# Attenuverter_v1_SCH.net
KiCad netlist of a schematic drawn in Altium Designer
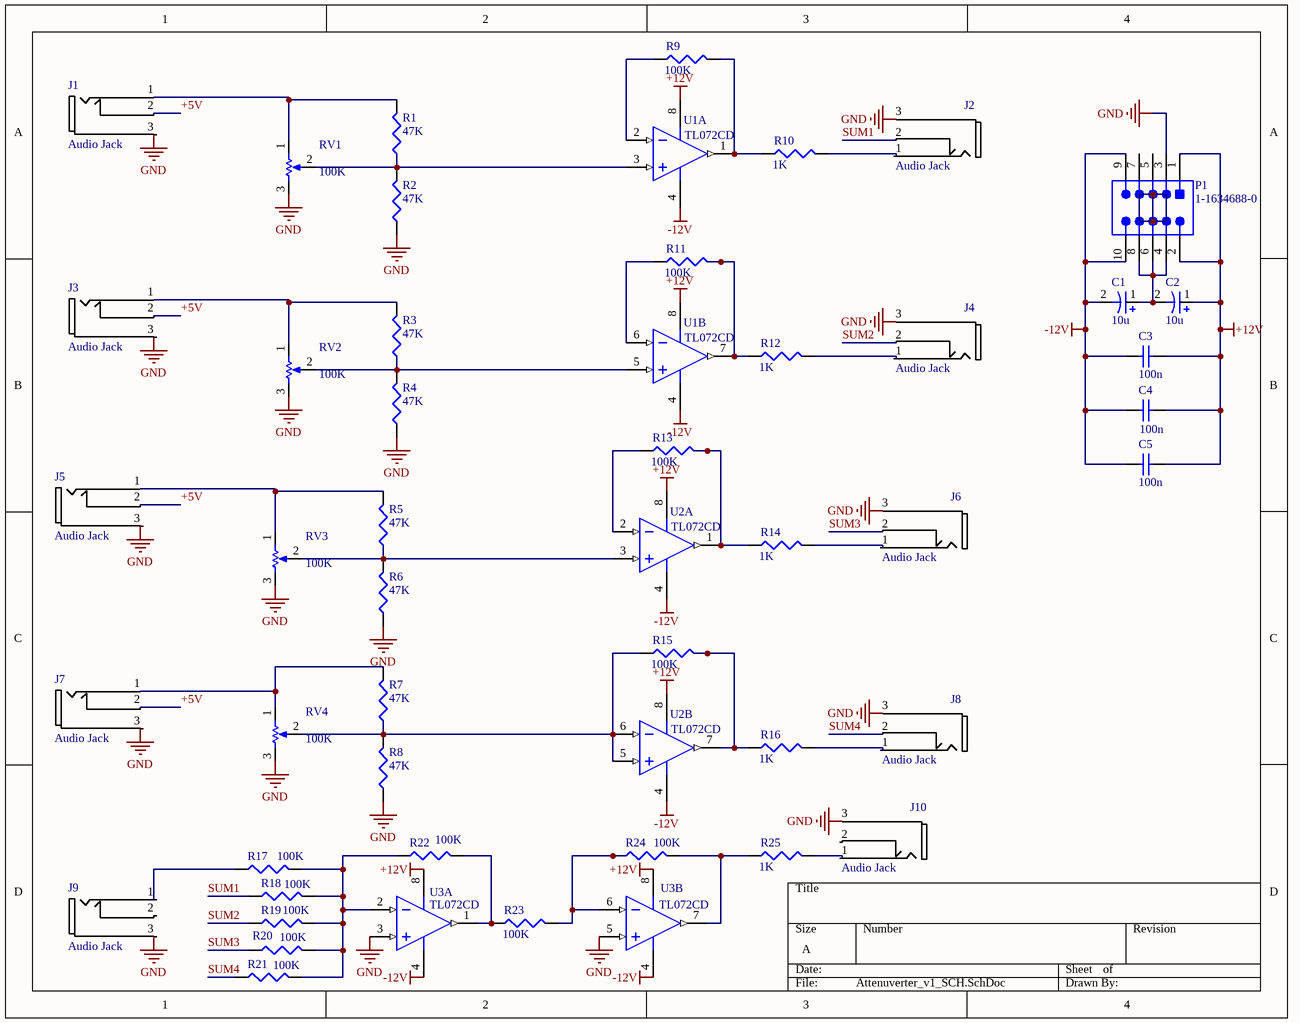
[diagram p0: Attenuverter_v1_SCH.SchDoc]

(export (version "E")
  (design (tool "Eeschema 10.0.6"))
  (components
    (comp (ref "C1")
      (value "10u")
      (footprint "SMD-1210C")
      (description "Polarized Capacitor (Radial)")
      (fields (field (name "Comment") "Cap Pol1") (field (name "PUBLISHER") "Altium Limited"))
      (libsource (lib "Miscellaneous Devices") (part "Cap Pol1"))
    )
    (comp (ref "C2")
      (value "10u")
      (footprint "SMD-1210C")
      (description "Polarized Capacitor (Radial)")
      (fields (field (name "Comment") "Cap Pol1") (field (name "PUBLISHER") "Altium Limited"))
      (libsource (lib "Miscellaneous Devices") (part "Cap Pol1"))
    )
    (comp (ref "C3")
      (value "100n")
      (footprint "0603")
      (description "Capacitor")
      (fields (field (name "Comment") "Cap") (field (name "PUBLISHER") "Altium Limited"))
      (libsource (lib "Miscellaneous Devices") (part "Cap"))
    )
    (comp (ref "C4")
      (value "100n")
      (footprint "0603")
      (description "Capacitor")
      (fields (field (name "Comment") "Cap") (field (name "PUBLISHER") "Altium Limited"))
      (libsource (lib "Miscellaneous Devices") (part "Cap"))
    )
    (comp (ref "C5")
      (value "100n")
      (footprint "0603")
      (description "Capacitor")
      (fields (field (name "Comment") "Cap") (field (name "PUBLISHER") "Altium Limited"))
      (libsource (lib "Miscellaneous Devices") (part "Cap"))
    )
    (comp (ref "J1")
      (value "Audio Jack")
      (footprint "Audio Jack")
      (libsource (lib "DIYSynth") (part "Audio Jack"))
    )
    (comp (ref "J2")
      (value "Audio Jack")
      (footprint "Audio Jack")
      (libsource (lib "DIYSynth") (part "Audio Jack"))
    )
    (comp (ref "J3")
      (value "Audio Jack")
      (footprint "Audio Jack")
      (libsource (lib "DIYSynth") (part "Audio Jack"))
    )
    (comp (ref "J4")
      (value "Audio Jack")
      (footprint "Audio Jack")
      (libsource (lib "DIYSynth") (part "Audio Jack"))
    )
    (comp (ref "J5")
      (value "Audio Jack")
      (footprint "Audio Jack")
      (libsource (lib "DIYSynth") (part "Audio Jack"))
    )
    (comp (ref "J6")
      (value "Audio Jack")
      (footprint "Audio Jack")
      (libsource (lib "DIYSynth") (part "Audio Jack"))
    )
    (comp (ref "J7")
      (value "Audio Jack")
      (footprint "Audio Jack")
      (libsource (lib "DIYSynth") (part "Audio Jack"))
    )
    (comp (ref "J8")
      (value "Audio Jack")
      (footprint "Audio Jack")
      (libsource (lib "DIYSynth") (part "Audio Jack"))
    )
    (comp (ref "J9")
      (value "Audio Jack")
      (footprint "Audio Jack")
      (libsource (lib "DIYSynth") (part "Audio Jack"))
    )
    (comp (ref "J10")
      (value "Audio Jack")
      (footprint "Audio Jack")
      (libsource (lib "DIYSynth") (part "Audio Jack"))
    )
    (comp (ref "P1")
      (value "1-1634688-0")
      (footprint "TECO-1-1634688-0-10_V")
      (fields (field (name "MANUFACTURER") "TE Connectivity"))
      (libsource (lib "Altium Content Vault") (part "CN-2P-M-R10"))
    )
    (comp (ref "R1")
      (value "47K")
      (footprint "J1-0603")
      (description "Resistor")
      (fields (field (name "Comment") "Res3") (field (name "PUBLISHER") "Altium Limited"))
      (libsource (lib "Miscellaneous Devices") (part "Res3"))
    )
    (comp (ref "R2")
      (value "47K")
      (footprint "J1-0603")
      (description "Resistor")
      (fields (field (name "Comment") "Res3") (field (name "PUBLISHER") "Altium Limited"))
      (libsource (lib "Miscellaneous Devices") (part "Res3"))
    )
    (comp (ref "R3")
      (value "47K")
      (footprint "J1-0603")
      (description "Resistor")
      (fields (field (name "Comment") "Res3") (field (name "PUBLISHER") "Altium Limited"))
      (libsource (lib "Miscellaneous Devices") (part "Res3"))
    )
    (comp (ref "R4")
      (value "47K")
      (footprint "J1-0603")
      (description "Resistor")
      (fields (field (name "Comment") "Res3") (field (name "PUBLISHER") "Altium Limited"))
      (libsource (lib "Miscellaneous Devices") (part "Res3"))
    )
    (comp (ref "R5")
      (value "47K")
      (footprint "J1-0603")
      (description "Resistor")
      (fields (field (name "Comment") "Res3") (field (name "PUBLISHER") "Altium Limited"))
      (libsource (lib "Miscellaneous Devices") (part "Res3"))
    )
    (comp (ref "R6")
      (value "47K")
      (footprint "J1-0603")
      (description "Resistor")
      (fields (field (name "Comment") "Res3") (field (name "PUBLISHER") "Altium Limited"))
      (libsource (lib "Miscellaneous Devices") (part "Res3"))
    )
    (comp (ref "R7")
      (value "47K")
      (footprint "J1-0603")
      (description "Resistor")
      (fields (field (name "Comment") "Res3") (field (name "PUBLISHER") "Altium Limited"))
      (libsource (lib "Miscellaneous Devices") (part "Res3"))
    )
    (comp (ref "R8")
      (value "47K")
      (footprint "J1-0603")
      (description "Resistor")
      (fields (field (name "Comment") "Res3") (field (name "PUBLISHER") "Altium Limited"))
      (libsource (lib "Miscellaneous Devices") (part "Res3"))
    )
    (comp (ref "R9")
      (value "100K")
      (footprint "J1-0603")
      (description "Resistor")
      (fields (field (name "Comment") "Res3") (field (name "PUBLISHER") "Altium Limited"))
      (libsource (lib "Miscellaneous Devices") (part "Res3"))
    )
    (comp (ref "R10")
      (value "1K")
      (footprint "J1-0603")
      (description "Resistor")
      (fields (field (name "Comment") "Res3") (field (name "PUBLISHER") "Altium Limited"))
      (libsource (lib "Miscellaneous Devices") (part "Res3"))
    )
    (comp (ref "R11")
      (value "100K")
      (footprint "J1-0603")
      (description "Resistor")
      (fields (field (name "Comment") "Res3") (field (name "PUBLISHER") "Altium Limited"))
      (libsource (lib "Miscellaneous Devices") (part "Res3"))
    )
    (comp (ref "R12")
      (value "1K")
      (footprint "J1-0603")
      (description "Resistor")
      (fields (field (name "Comment") "Res3") (field (name "PUBLISHER") "Altium Limited"))
      (libsource (lib "Miscellaneous Devices") (part "Res3"))
    )
    (comp (ref "R13")
      (value "100K")
      (footprint "J1-0603")
      (description "Resistor")
      (fields (field (name "Comment") "Res3") (field (name "PUBLISHER") "Altium Limited"))
      (libsource (lib "Miscellaneous Devices") (part "Res3"))
    )
    (comp (ref "R14")
      (value "1K")
      (footprint "J1-0603")
      (description "Resistor")
      (fields (field (name "Comment") "Res3") (field (name "PUBLISHER") "Altium Limited"))
      (libsource (lib "Miscellaneous Devices") (part "Res3"))
    )
    (comp (ref "R15")
      (value "100K")
      (footprint "J1-0603")
      (description "Resistor")
      (fields (field (name "Comment") "Res3") (field (name "PUBLISHER") "Altium Limited"))
      (libsource (lib "Miscellaneous Devices") (part "Res3"))
    )
    (comp (ref "R16")
      (value "1K")
      (footprint "J1-0603")
      (description "Resistor")
      (fields (field (name "Comment") "Res3") (field (name "PUBLISHER") "Altium Limited"))
      (libsource (lib "Miscellaneous Devices") (part "Res3"))
    )
    (comp (ref "R17")
      (value "100K")
      (footprint "J1-0603")
      (description "Resistor")
      (fields (field (name "Comment") "Res3") (field (name "PUBLISHER") "Altium Limited"))
      (libsource (lib "Miscellaneous Devices") (part "Res3"))
    )
    (comp (ref "R18")
      (value "100K")
      (footprint "J1-0603")
      (description "Resistor")
      (fields (field (name "Comment") "Res3") (field (name "PUBLISHER") "Altium Limited"))
      (libsource (lib "Miscellaneous Devices") (part "Res3"))
    )
    (comp (ref "R19")
      (value "100K")
      (footprint "J1-0603")
      (description "Resistor")
      (fields (field (name "Comment") "Res3") (field (name "PUBLISHER") "Altium Limited"))
      (libsource (lib "Miscellaneous Devices") (part "Res3"))
    )
    (comp (ref "R20")
      (value "100K")
      (footprint "J1-0603")
      (description "Resistor")
      (fields (field (name "Comment") "Res3") (field (name "PUBLISHER") "Altium Limited"))
      (libsource (lib "Miscellaneous Devices") (part "Res3"))
    )
    (comp (ref "R21")
      (value "100K")
      (footprint "J1-0603")
      (description "Resistor")
      (fields (field (name "Comment") "Res3") (field (name "PUBLISHER") "Altium Limited"))
      (libsource (lib "Miscellaneous Devices") (part "Res3"))
    )
    (comp (ref "R22")
      (value "100K")
      (footprint "J1-0603")
      (description "Resistor")
      (fields (field (name "Comment") "Res3") (field (name "PUBLISHER") "Altium Limited"))
      (libsource (lib "Miscellaneous Devices") (part "Res3"))
    )
    (comp (ref "R23")
      (value "100K")
      (footprint "J1-0603")
      (description "Resistor")
      (fields (field (name "Comment") "Res3") (field (name "PUBLISHER") "Altium Limited"))
      (libsource (lib "Miscellaneous Devices") (part "Res3"))
    )
    (comp (ref "R24")
      (value "100K")
      (footprint "J1-0603")
      (description "Resistor")
      (fields (field (name "Comment") "Res3") (field (name "PUBLISHER") "Altium Limited"))
      (libsource (lib "Miscellaneous Devices") (part "Res3"))
    )
    (comp (ref "R25")
      (value "1K")
      (footprint "J1-0603")
      (description "Resistor")
      (fields (field (name "Comment") "Res3") (field (name "PUBLISHER") "Altium Limited"))
      (libsource (lib "Miscellaneous Devices") (part "Res3"))
    )
    (comp (ref "RV1")
      (value "100K")
      (footprint "VR5")
      (description "Potentiometer")
      (fields (field (name "Comment") "RPot") (field (name "PUBLISHER") "Altium Limited"))
      (libsource (lib "Miscellaneous Devices") (part "RPot"))
    )
    (comp (ref "RV2")
      (value "100K")
      (footprint "VR5")
      (description "Potentiometer")
      (fields (field (name "Comment") "RPot") (field (name "PUBLISHER") "Altium Limited"))
      (libsource (lib "Miscellaneous Devices") (part "RPot"))
    )
    (comp (ref "RV3")
      (value "100K")
      (footprint "VR5")
      (description "Potentiometer")
      (fields (field (name "Comment") "RPot") (field (name "PUBLISHER") "Altium Limited"))
      (libsource (lib "Miscellaneous Devices") (part "RPot"))
    )
    (comp (ref "RV4")
      (value "100K")
      (footprint "VR5")
      (description "Potentiometer")
      (fields (field (name "Comment") "RPot") (field (name "PUBLISHER") "Altium Limited"))
      (libsource (lib "Miscellaneous Devices") (part "RPot"))
    )
    (comp (ref "U1")
      (value "TL072CD")
      (footprint "D0008A_M")
      (fields (field (name "MANUFACTURER") "Texas Instruments"))
      (libsource (lib "Altium Content Vault") (part "TI-AMP-D6-2-8_D"))
    )
    (comp (ref "U2")
      (value "TL072CD")
      (footprint "D0008A_M")
      (fields (field (name "MANUFACTURER") "Texas Instruments"))
      (libsource (lib "Altium Content Vault") (part "TI-AMP-D6-2-8_D"))
    )
    (comp (ref "U3")
      (value "TL072CD")
      (footprint "D0008A_M")
      (fields (field (name "MANUFACTURER") "Texas Instruments"))
      (libsource (lib "Altium Content Vault") (part "TI-AMP-D6-2-8_D"))
    )
  )
  (nets
    (net (code "1") (name "+12V") (class "Default")
      (node (ref "C2") (pin "1") (pinfunction "1_1") (pintype "passive"))
      (node (ref "C3") (pin "1") (pinfunction "1_1") (pintype "passive"))
      (node (ref "C4") (pin "1") (pinfunction "1_1") (pintype "passive"))
      (node (ref "C5") (pin "1") (pinfunction "1_1") (pintype "passive"))
      (node (ref "P1") (pin "1") (pinfunction "1_1") (pintype "passive"))
      (node (ref "P1") (pin "2") (pinfunction "2_2") (pintype "passive"))
      (node (ref "U1") (pin "8") (pinfunction "VCC+_8") (pintype "power_in"))
      (node (ref "U2") (pin "8") (pinfunction "VCC+_8") (pintype "power_in"))
      (node (ref "U3") (pin "8") (pinfunction "VCC+_8") (pintype "power_in"))
    )
    (net (code "2") (name "-12V") (class "Default")
      (node (ref "C1") (pin "2") (pinfunction "2_2") (pintype "passive"))
      (node (ref "C3") (pin "2") (pinfunction "2_2") (pintype "passive"))
      (node (ref "C4") (pin "2") (pinfunction "2_2") (pintype "passive"))
      (node (ref "C5") (pin "2") (pinfunction "2_2") (pintype "passive"))
      (node (ref "P1") (pin "10") (pinfunction "10_10") (pintype "passive"))
      (node (ref "P1") (pin "9") (pinfunction "9_9") (pintype "passive"))
      (node (ref "U1") (pin "4") (pinfunction "VCC-_4") (pintype "power_in"))
      (node (ref "U2") (pin "4") (pinfunction "VCC-_4") (pintype "power_in"))
      (node (ref "U3") (pin "4") (pinfunction "VCC-_4") (pintype "power_in"))
    )
    (net (code "3") (name "/+5V") (class "Default")
      (node (ref "J1") (pin "2") (pinfunction "THRU_2") (pintype "passive"))
      (node (ref "J3") (pin "2") (pinfunction "THRU_2") (pintype "passive"))
      (node (ref "J5") (pin "2") (pinfunction "THRU_2") (pintype "passive"))
      (node (ref "J7") (pin "2") (pinfunction "THRU_2") (pintype "passive"))
    )
    (net (code "4") (name "/SUM1") (class "Default")
      (node (ref "J2") (pin "2") (pinfunction "THRU_2") (pintype "passive"))
      (node (ref "R18") (pin "1") (pinfunction "1_1") (pintype "passive"))
    )
    (net (code "5") (name "/SUM2") (class "Default")
      (node (ref "J4") (pin "2") (pinfunction "THRU_2") (pintype "passive"))
      (node (ref "R19") (pin "1") (pinfunction "1_1") (pintype "passive"))
    )
    (net (code "6") (name "/SUM3") (class "Default")
      (node (ref "J6") (pin "2") (pinfunction "THRU_2") (pintype "passive"))
      (node (ref "R20") (pin "1") (pinfunction "1_1") (pintype "passive"))
    )
    (net (code "7") (name "/SUM4") (class "Default")
      (node (ref "J8") (pin "2") (pinfunction "THRU_2") (pintype "passive"))
      (node (ref "R21") (pin "1") (pinfunction "1_1") (pintype "passive"))
    )
    (net (code "8") (name "GND") (class "Default")
      (node (ref "J1") (pin "3") (pinfunction "G_3") (pintype "passive"))
      (node (ref "J10") (pin "3") (pinfunction "G_3") (pintype "passive"))
      (node (ref "J2") (pin "3") (pinfunction "G_3") (pintype "passive"))
      (node (ref "J3") (pin "3") (pinfunction "G_3") (pintype "passive"))
      (node (ref "J4") (pin "3") (pinfunction "G_3") (pintype "passive"))
      (node (ref "J5") (pin "3") (pinfunction "G_3") (pintype "passive"))
      (node (ref "J6") (pin "3") (pinfunction "G_3") (pintype "passive"))
      (node (ref "J7") (pin "3") (pinfunction "G_3") (pintype "passive"))
      (node (ref "J8") (pin "3") (pinfunction "G_3") (pintype "passive"))
      (node (ref "J9") (pin "3") (pinfunction "G_3") (pintype "passive"))
      (node (ref "P1") (pin "3") (pinfunction "3_3") (pintype "passive"))
      (node (ref "R2") (pin "1") (pinfunction "1_1") (pintype "passive"))
      (node (ref "R4") (pin "1") (pinfunction "1_1") (pintype "passive"))
      (node (ref "R6") (pin "1") (pinfunction "1_1") (pintype "passive"))
      (node (ref "R8") (pin "1") (pinfunction "1_1") (pintype "passive"))
      (node (ref "RV1") (pin "3") (pinfunction "TOP_3") (pintype "passive"))
      (node (ref "RV2") (pin "3") (pinfunction "TOP_3") (pintype "passive"))
      (node (ref "RV3") (pin "3") (pinfunction "TOP_3") (pintype "passive"))
      (node (ref "RV4") (pin "3") (pinfunction "TOP_3") (pintype "passive"))
      (node (ref "U3") (pin "3") (pinfunction "IN1+_3") (pintype "input"))
      (node (ref "U3") (pin "5") (pinfunction "IN2+_5") (pintype "input"))
    )
    (net (code "9") (name "Net-(C1-Pad1)") (class "Default")
      (node (ref "C1") (pin "1") (pinfunction "1_1") (pintype "passive"))
      (node (ref "C2") (pin "2") (pinfunction "2_2") (pintype "passive"))
      (node (ref "P1") (pin "4") (pinfunction "4_4") (pintype "passive"))
      (node (ref "P1") (pin "6") (pinfunction "6_6") (pintype "passive"))
      (node (ref "P1") (pin "8") (pinfunction "8_8") (pintype "passive"))
    )
    (net (code "10") (name "Net-(J1-IN)") (class "Default")
      (node (ref "J1") (pin "1") (pinfunction "IN_1") (pintype "passive"))
      (node (ref "R1") (pin "2") (pinfunction "2_2") (pintype "passive"))
      (node (ref "RV1") (pin "1") (pinfunction "BOT_1") (pintype "passive"))
    )
    (net (code "11") (name "Net-(J2-IN)") (class "Default")
      (node (ref "J2") (pin "1") (pinfunction "IN_1") (pintype "passive"))
      (node (ref "R10") (pin "2") (pinfunction "2_2") (pintype "passive"))
    )
    (net (code "12") (name "Net-(J3-IN)") (class "Default")
      (node (ref "J3") (pin "1") (pinfunction "IN_1") (pintype "passive"))
      (node (ref "R3") (pin "2") (pinfunction "2_2") (pintype "passive"))
      (node (ref "RV2") (pin "1") (pinfunction "BOT_1") (pintype "passive"))
    )
    (net (code "13") (name "Net-(J4-IN)") (class "Default")
      (node (ref "J4") (pin "1") (pinfunction "IN_1") (pintype "passive"))
      (node (ref "R12") (pin "2") (pinfunction "2_2") (pintype "passive"))
    )
    (net (code "14") (name "Net-(J5-IN)") (class "Default")
      (node (ref "J5") (pin "1") (pinfunction "IN_1") (pintype "passive"))
      (node (ref "R5") (pin "2") (pinfunction "2_2") (pintype "passive"))
      (node (ref "RV3") (pin "1") (pinfunction "BOT_1") (pintype "passive"))
    )
    (net (code "15") (name "Net-(J6-IN)") (class "Default")
      (node (ref "J6") (pin "1") (pinfunction "IN_1") (pintype "passive"))
      (node (ref "R14") (pin "2") (pinfunction "2_2") (pintype "passive"))
    )
    (net (code "16") (name "Net-(J7-IN)") (class "Default")
      (node (ref "J7") (pin "1") (pinfunction "IN_1") (pintype "passive"))
      (node (ref "R7") (pin "2") (pinfunction "2_2") (pintype "passive"))
      (node (ref "RV4") (pin "1") (pinfunction "BOT_1") (pintype "passive"))
    )
    (net (code "17") (name "Net-(J8-IN)") (class "Default")
      (node (ref "J8") (pin "1") (pinfunction "IN_1") (pintype "passive"))
      (node (ref "R16") (pin "2") (pinfunction "2_2") (pintype "passive"))
    )
    (net (code "18") (name "Net-(J9-IN)") (class "Default")
      (node (ref "J9") (pin "1") (pinfunction "IN_1") (pintype "passive"))
      (node (ref "R17") (pin "1") (pinfunction "1_1") (pintype "passive"))
    )
    (net (code "19") (name "Net-(J10-IN)") (class "Default")
      (node (ref "J10") (pin "1") (pinfunction "IN_1") (pintype "passive"))
      (node (ref "R25") (pin "2") (pinfunction "2_2") (pintype "passive"))
    )
    (net (code "20") (name "Net-(RV1-TAP)") (class "Default")
      (node (ref "R1") (pin "1") (pinfunction "1_1") (pintype "passive"))
      (node (ref "R2") (pin "2") (pinfunction "2_2") (pintype "passive"))
      (node (ref "RV1") (pin "2") (pinfunction "TAP_2") (pintype "passive"))
      (node (ref "U1") (pin "3") (pinfunction "IN1+_3") (pintype "input"))
    )
    (net (code "21") (name "Net-(RV2-TAP)") (class "Default")
      (node (ref "R3") (pin "1") (pinfunction "1_1") (pintype "passive"))
      (node (ref "R4") (pin "2") (pinfunction "2_2") (pintype "passive"))
      (node (ref "RV2") (pin "2") (pinfunction "TAP_2") (pintype "passive"))
      (node (ref "U1") (pin "5") (pinfunction "IN2+_5") (pintype "input"))
    )
    (net (code "22") (name "Net-(RV3-TAP)") (class "Default")
      (node (ref "R5") (pin "1") (pinfunction "1_1") (pintype "passive"))
      (node (ref "R6") (pin "2") (pinfunction "2_2") (pintype "passive"))
      (node (ref "RV3") (pin "2") (pinfunction "TAP_2") (pintype "passive"))
      (node (ref "U2") (pin "3") (pinfunction "IN1+_3") (pintype "input"))
    )
    (net (code "23") (name "Net-(RV4-TAP)") (class "Default")
      (node (ref "R15") (pin "1") (pinfunction "1_1") (pintype "passive"))
      (node (ref "R7") (pin "1") (pinfunction "1_1") (pintype "passive"))
      (node (ref "R8") (pin "2") (pinfunction "2_2") (pintype "passive"))
      (node (ref "RV4") (pin "2") (pinfunction "TAP_2") (pintype "passive"))
      (node (ref "U2") (pin "5") (pinfunction "IN2+_5") (pintype "input"))
      (node (ref "U2") (pin "6") (pinfunction "IN2-_6") (pintype "input"))
    )
    (net (code "24") (name "Net-(U1A-IN1-)") (class "Default")
      (node (ref "R9") (pin "1") (pinfunction "1_1") (pintype "passive"))
      (node (ref "U1") (pin "2") (pinfunction "IN1-_2") (pintype "input"))
    )
    (net (code "25") (name "Net-(U1A-OUT1)") (class "Default")
      (node (ref "R10") (pin "1") (pinfunction "1_1") (pintype "passive"))
      (node (ref "R9") (pin "2") (pinfunction "2_2") (pintype "passive"))
      (node (ref "U1") (pin "1") (pinfunction "OUT1_1") (pintype "output"))
    )
    (net (code "26") (name "Net-(U1B-IN2-)") (class "Default")
      (node (ref "R11") (pin "1") (pinfunction "1_1") (pintype "passive"))
      (node (ref "U1") (pin "6") (pinfunction "IN2-_6") (pintype "input"))
    )
    (net (code "27") (name "Net-(U1B-OUT2)") (class "Default")
      (node (ref "R11") (pin "2") (pinfunction "2_2") (pintype "passive"))
      (node (ref "R12") (pin "1") (pinfunction "1_1") (pintype "passive"))
      (node (ref "U1") (pin "7") (pinfunction "OUT2_7") (pintype "output"))
    )
    (net (code "28") (name "Net-(U2A-IN1-)") (class "Default")
      (node (ref "R13") (pin "1") (pinfunction "1_1") (pintype "passive"))
      (node (ref "U2") (pin "2") (pinfunction "IN1-_2") (pintype "input"))
    )
    (net (code "29") (name "Net-(U2A-OUT1)") (class "Default")
      (node (ref "R13") (pin "2") (pinfunction "2_2") (pintype "passive"))
      (node (ref "R14") (pin "1") (pinfunction "1_1") (pintype "passive"))
      (node (ref "U2") (pin "1") (pinfunction "OUT1_1") (pintype "output"))
    )
    (net (code "30") (name "Net-(U2B-OUT2)") (class "Default")
      (node (ref "R15") (pin "2") (pinfunction "2_2") (pintype "passive"))
      (node (ref "R16") (pin "1") (pinfunction "1_1") (pintype "passive"))
      (node (ref "U2") (pin "7") (pinfunction "OUT2_7") (pintype "output"))
    )
    (net (code "31") (name "Net-(U3A-IN1-)") (class "Default")
      (node (ref "R17") (pin "2") (pinfunction "2_2") (pintype "passive"))
      (node (ref "R18") (pin "2") (pinfunction "2_2") (pintype "passive"))
      (node (ref "R19") (pin "2") (pinfunction "2_2") (pintype "passive"))
      (node (ref "R20") (pin "2") (pinfunction "2_2") (pintype "passive"))
      (node (ref "R21") (pin "2") (pinfunction "2_2") (pintype "passive"))
      (node (ref "R22") (pin "1") (pinfunction "1_1") (pintype "passive"))
      (node (ref "U3") (pin "2") (pinfunction "IN1-_2") (pintype "input"))
    )
    (net (code "32") (name "Net-(U3A-OUT1)") (class "Default")
      (node (ref "R22") (pin "2") (pinfunction "2_2") (pintype "passive"))
      (node (ref "R23") (pin "1") (pinfunction "1_1") (pintype "passive"))
      (node (ref "U3") (pin "1") (pinfunction "OUT1_1") (pintype "output"))
    )
    (net (code "33") (name "Net-(U3B-IN2-)") (class "Default")
      (node (ref "R23") (pin "2") (pinfunction "2_2") (pintype "passive"))
      (node (ref "R24") (pin "1") (pinfunction "1_1") (pintype "passive"))
      (node (ref "U3") (pin "6") (pinfunction "IN2-_6") (pintype "input"))
    )
    (net (code "34") (name "Net-(U3B-OUT2)") (class "Default")
      (node (ref "R24") (pin "2") (pinfunction "2_2") (pintype "passive"))
      (node (ref "R25") (pin "1") (pinfunction "1_1") (pintype "passive"))
      (node (ref "U3") (pin "7") (pinfunction "OUT2_7") (pintype "output"))
    )
    (net (code "35") (name "unconnected-(J9-THRU-Pad2)") (class "Default")
      (node (ref "J9") (pin "2") (pinfunction "THRU_2") (pintype "passive"))
    )
    (net (code "36") (name "unconnected-(J10-THRU-Pad2)") (class "Default")
      (node (ref "J10") (pin "2") (pinfunction "THRU_2") (pintype "passive"))
    )
    (net (code "37") (name "unconnected-(P1-Pad5)") (class "Default")
      (node (ref "P1") (pin "5") (pinfunction "5_5") (pintype "passive"))
    )
    (net (code "38") (name "unconnected-(P1-Pad7)") (class "Default")
      (node (ref "P1") (pin "7") (pinfunction "7_7") (pintype "passive"))
    )
  )
)
